# MCU_IO.net
KiCad netlist of a schematic drawn in Altium Designer
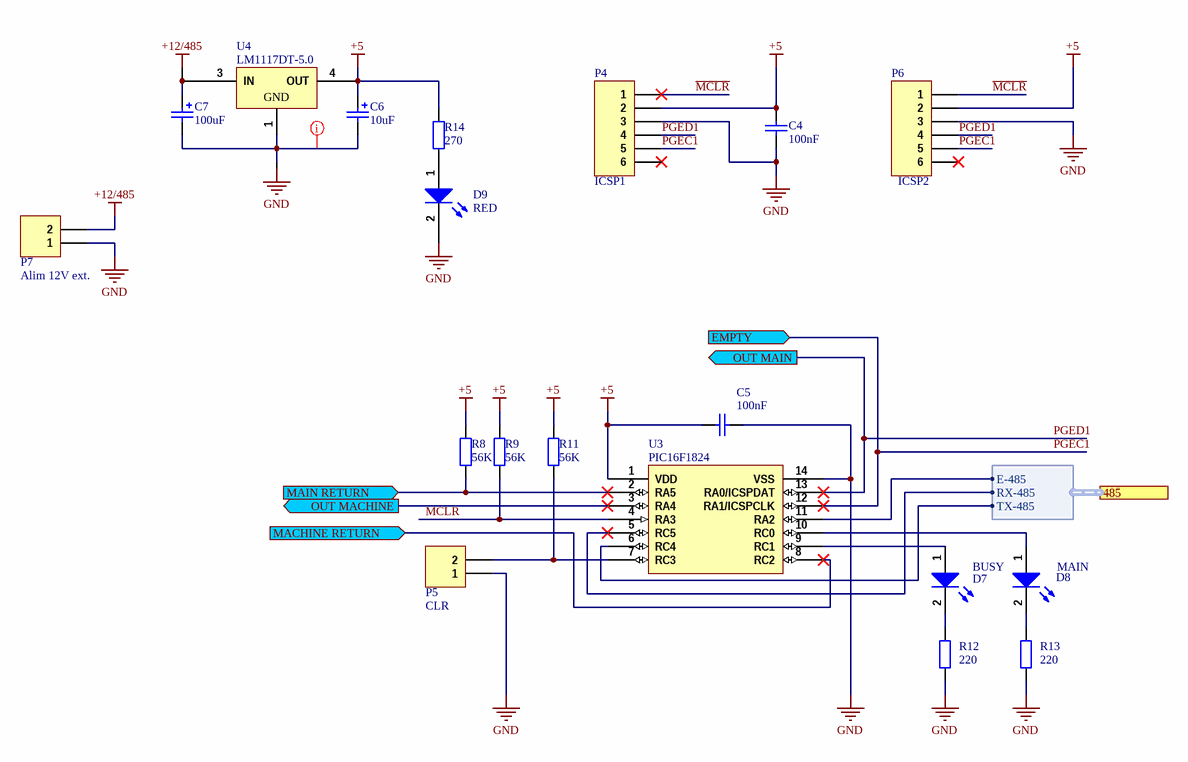
[diagram p0: MCU IO.SchDoc]

(export (version "E")
  (design (tool "Eeschema 10.0.6"))
  (components
    (comp (ref "C4")
      (value "100nF")
      (footprint "SYLANN:C0805")
      (description "Capacitor")
      (fields
        (field (name "MANUFACTURER") "MULTICOMP")
        (field (name "MANUFACTURER PART NUMBER") "MCCA000296")
      )
      (libsource (lib "Capacitors") (part "Cap 0805 100nF"))
    )
    (comp (ref "C5")
      (value "100nF")
      (footprint "SYLANN:C0805")
      (description "Capacitor")
      (fields
        (field (name "MANUFACTURER") "MULTICOMP")
        (field (name "MANUFACTURER PART NUMBER") "MCCA000296")
      )
      (libsource (lib "BRA") (part "Cap 0805 100nF"))
    )
    (comp (ref "C6")
      (value "10uF")
      (footprint "SYLANN:KEMET_4")
      (description "Polarized Capacitor")
      (fields
        (field (name "MANUFACTURER") "KEMET")
        (field (name "MANUFACTURER PART NUMBER") "EXV106M025A9BAA")
      )
      (libsource (lib "BRA") (part "Cap Pol 10uF"))
    )
    (comp (ref "C7")
      (value "100uF")
      (footprint "SYLANN:Kemet_63")
      (description "Polarized Capacitor")
      (fields
        (field (name "MANUFACTURER") "EPCOS")
        (field (name "MANUFACTURER PART NUMBER") "B41142A4107M")
        (field (name "HAUTEUR") "7.7")
        (field (name "LONGUEUR/HAUTEUR") "7.7")
      )
      (libsource (lib "BRA") (part "Cap Pol 100uF"))
    )
    (comp (ref "D7")
      (value "HSMH-C190")
      (footprint "0603-LEDR")
      (description "Surface Mount Chip LED, Red")
      (fields
        (field (name "MANUFACTURER") "AVAGO TECHNOLOGIES")
        (field (name "MANUFACTURER PART NUMBER") "HSMH-C190.")
        (field (name "INDICATOR") "BUSY")
        (field (name "LONGUEUR/HAUTEUR") "1.6")
      )
      (libsource (lib "BRA") (part "HSMH-C190"))
    )
    (comp (ref "D8")
      (value "MAIN")
      (footprint "0603-LEDV")
      (description "Surface Mount Chip GREEN")
      (fields
        (field (name "MANUFACTURER") "Broadcom Avago")
        (field (name "MANUFACTURER PART NUMBER") "HSMG-C190")
      )
      (libsource (lib "BRA") (part "HSMG-C190"))
    )
    (comp (ref "D9")
      (value "HSMH-C190")
      (footprint "0603-LEDR")
      (description "Surface Mount Chip LED, Red")
      (fields
        (field (name "MANUFACTURER") "AVAGO TECHNOLOGIES")
        (field (name "MANUFACTURER PART NUMBER") "HSMH-C190.")
        (field (name "COULEUR") "RED")
        (field (name "LONGUEUR/HAUTEUR") "1.6")
      )
      (libsource (lib "Avago Optoelectronic LED") (part "HSMH-C190"))
    )
    (comp (ref "P4")
      (value "ICSP1")
      (footprint "TC2030")
      (description "Header, 6-Pin")
      (fields (field (name "MANUFACTURER") "HARWIN") (field (name "MANUFACTURER PART NUMBER") "M20-8770642"))
      (libsource (lib "Miscellaneous Connectors") (part "Header 6"))
    )
    (comp (ref "P5")
      (value "CLR")
      (footprint "SYLANN:M20_1X2")
      (description "Header, 2-Pin")
      (fields
        (field (name "MANUFACTURER") "HARWIN")
        (field (name "MANUFACTURER PART NUMBER") "M20-8770242")
        (field (name "PUBLISHER") "Altium Limited")
      )
      (libsource (lib "Miscellaneous Connectors") (part "Header 2"))
    )
    (comp (ref "P6")
      (value "ICSP2")
      (footprint "6SIP100")
      (description "Header, 6-Pin")
      (fields
        (field (name "MANUFACTURER") "TE CONNECTIVITY / AMP")
        (field (name "MANUFACTURER PART NUMBER") "4-103321-8.")
      )
      (libsource (lib "Miscellaneous Connectors") (part "Header 6"))
    )
    (comp (ref "P7")
      (value "Alim 12V ext.")
      (footprint "CO2P508")
      (description "Header, 2-Pin")
      (libsource (lib "Miscellaneous Connectors") (part "Header 2"))
    )
    (comp (ref "R8")
      (value "56K")
      (footprint "R0805")
      (description "Resistor")
      (fields
        (field (name "MANUFACTURER") "MULTICOMP")
        (field (name "MANUFACTURER PART NUMBER") "MC0.1W08051%56KFR")
      )
      (libsource (lib "BRA") (part "Resistor 0805 56K"))
    )
    (comp (ref "R9")
      (value "56K")
      (footprint "R0805")
      (description "Resistor")
      (fields
        (field (name "MANUFACTURER") "MULTICOMP")
        (field (name "MANUFACTURER PART NUMBER") "MC0.1W08051%56KFR")
      )
      (libsource (lib "BRA") (part "Resistor 0805 56K"))
    )
    (comp (ref "R11")
      (value "56K")
      (footprint "R0805")
      (description "Resistor")
      (fields
        (field (name "MANUFACTURER") "MULTICOMP")
        (field (name "MANUFACTURER PART NUMBER") "MC0.1W08051%56KFR")
      )
      (libsource (lib "BRA") (part "Resistor 0805 56K"))
    )
    (comp (ref "R12")
      (value "220")
      (footprint "R0805")
      (description "Resistor")
      (fields
        (field (name "MANUFACTURER") "MULTICOMP")
        (field (name "MANUFACTURER PART NUMBER") "MC01W08051220R")
      )
      (libsource (lib "BRA") (part "Resistor 0805 220"))
    )
    (comp (ref "R13")
      (value "220")
      (footprint "R0805")
      (description "Resistor")
      (fields
        (field (name "MANUFACTURER") "MULTICOMP")
        (field (name "MANUFACTURER PART NUMBER") "MC01W08051220R")
      )
      (libsource (lib "BRA") (part "Resistor 0805 220"))
    )
    (comp (ref "R14")
      (value "270")
      (footprint "R0805")
      (description "Resistor")
      (fields
        (field (name "MANUFACTURER") "MULTICOMP")
        (field (name "MANUFACTURER PART NUMBER") "MC0.1W08051%1KFR")
      )
      (libsource (lib "BRA") (part "Resistor 0805 1K"))
    )
    (comp (ref "U3")
      (value "PIC16F1824")
      (footprint "so-14")
      (description "14 Pin Flash Microcontrollers with XLP Technology")
      (fields
        (field (name "MANUFACTURER") "MICROCHIP")
        (field (name "MANUFACTURER PART NUMBER") "PIC16F1824-I/SL")
      )
      (libsource (lib "BRA") (part "PIC16(L)F1824"))
    )
    (comp (ref "U4")
      (value "LM1117DT-5.0")
      (footprint "SOT223")
      (description "800mA Low-Dropout Linear Regulator, 3-pin TO-252")
      (fields
        (field (name "MANUFACTURER") "TEXAS INSTRUMENTS")
        (field (name "MANUFACTURER PART NUMBER") "LM1117MP-5.0")
      )
      (libsource (lib "NSC LDO") (part "LM1117DT-5.0"))
    )
  )
  (nets
    (net (code "2") (name "+5") (class "Default")
      (node (ref "C4") (pin "2") (pinfunction "2_2") (pintype "passive"))
      (node (ref "C5") (pin "2") (pinfunction "2_2") (pintype "passive"))
      (node (ref "C6") (pin "1") (pinfunction "1_1") (pintype "passive"))
      (node (ref "P4") (pin "2") (pinfunction "2_2") (pintype "passive"))
      (node (ref "P6") (pin "2") (pinfunction "2_2") (pintype "passive"))
      (node (ref "R11") (pin "2") (pinfunction "2_2") (pintype "passive"))
      (node (ref "R14") (pin "2") (pinfunction "2_2") (pintype "passive"))
      (node (ref "R8") (pin "2") (pinfunction "2_2") (pintype "passive"))
      (node (ref "R9") (pin "2") (pinfunction "2_2") (pintype "passive"))
      (node (ref "U3") (pin "1") (pinfunction "VDD_1") (pintype "power_in"))
      (node (ref "U4") (pin "4") (pinfunction "OUT_4") (pintype "power_in"))
    )
    (net (code "3") (name "+12{slash}485") (class "Default")
      (node (ref "C7") (pin "1") (pinfunction "1_1") (pintype "passive"))
      (node (ref "P7") (pin "2") (pinfunction "2_2") (pintype "passive"))
      (node (ref "U4") (pin "3") (pinfunction "IN_3") (pintype "power_in"))
    )
    (net (code "4") (name "/E-485") (class "Default")
      (node (ref "U3") (pin "11") (pinfunction "RA2_11") (pintype "bidirectional"))
    )
    (net (code "5") (name "/MACHINE RETURN") (class "Default")
      (node (ref "U3") (pin "8") (pinfunction "RC2_8") (pintype "bidirectional+no_connect"))
    )
    (net (code "6") (name "/MAIN RETURN") (class "Default")
      (node (ref "R8") (pin "1") (pinfunction "1_1") (pintype "passive"))
      (node (ref "U3") (pin "2") (pinfunction "RA5_2") (pintype "bidirectional"))
    )
    (net (code "7") (name "/OUT MACHINE") (class "Default")
      (node (ref "U3") (pin "3") (pinfunction "RA4_3") (pintype "bidirectional+no_connect"))
    )
    (net (code "8") (name "/PGEC1") (class "Default")
      (node (ref "P4") (pin "5") (pinfunction "5_5") (pintype "passive"))
      (node (ref "P6") (pin "5") (pinfunction "5_5") (pintype "passive"))
      (node (ref "U3") (pin "12") (pinfunction "RA1/ICSPCLK_12") (pintype "bidirectional"))
    )
    (net (code "9") (name "/PGED1") (class "Default")
      (node (ref "P4") (pin "4") (pinfunction "4_4") (pintype "passive"))
      (node (ref "P6") (pin "4") (pinfunction "4_4") (pintype "passive"))
      (node (ref "U3") (pin "13") (pinfunction "RA0/ICSPDAT_13") (pintype "bidirectional"))
    )
    (net (code "10") (name "/RX-485") (class "Default")
      (node (ref "U3") (pin "5") (pinfunction "RC5_5") (pintype "bidirectional+no_connect"))
    )
    (net (code "11") (name "/TX-485") (class "Default")
      (node (ref "U3") (pin "6") (pinfunction "RC4_6") (pintype "bidirectional"))
    )
    (net (code "13") (name "/~{MCLR}") (class "Default")
      (node (ref "P4") (pin "1") (pinfunction "1_1") (pintype "passive"))
      (node (ref "P6") (pin "1") (pinfunction "1_1") (pintype "passive"))
      (node (ref "R9") (pin "1") (pinfunction "1_1") (pintype "passive"))
      (node (ref "U3") (pin "4") (pinfunction "RA3_4") (pintype "input"))
    )
    (net (code "14") (name "GND") (class "Default")
      (node (ref "C4") (pin "1") (pinfunction "1_1") (pintype "passive"))
      (node (ref "C5") (pin "1") (pinfunction "1_1") (pintype "passive"))
      (node (ref "C6") (pin "2") (pinfunction "2_2") (pintype "passive"))
      (node (ref "C7") (pin "2") (pinfunction "2_2") (pintype "passive"))
      (node (ref "D9") (pin "2") (pinfunction "K_2") (pintype "passive"))
      (node (ref "P4") (pin "3") (pinfunction "3_3") (pintype "passive"))
      (node (ref "P5") (pin "1") (pinfunction "1_1") (pintype "passive"))
      (node (ref "P6") (pin "3") (pinfunction "3_3") (pintype "passive"))
      (node (ref "P7") (pin "1") (pinfunction "1_1") (pintype "passive"))
      (node (ref "R12") (pin "1") (pinfunction "1_1") (pintype "passive"))
      (node (ref "R13") (pin "1") (pinfunction "1_1") (pintype "passive"))
      (node (ref "U3") (pin "14") (pinfunction "VSS_14") (pintype "power_in"))
      (node (ref "U4") (pin "1") (pinfunction "GND_1") (pintype "power_in"))
    )
    (net (code "15") (name "Net-(D7-A)") (class "Default")
      (node (ref "D7") (pin "1") (pinfunction "A_1") (pintype "passive"))
      (node (ref "U3") (pin "9") (pinfunction "RC1_9") (pintype "bidirectional"))
    )
    (net (code "16") (name "Net-(D7-K)") (class "Default")
      (node (ref "D7") (pin "2") (pinfunction "K_2") (pintype "passive"))
      (node (ref "R12") (pin "2") (pinfunction "2_2") (pintype "passive"))
    )
    (net (code "17") (name "Net-(D8-A)") (class "Default")
      (node (ref "D8") (pin "1") (pinfunction "A_1") (pintype "passive"))
      (node (ref "U3") (pin "10") (pinfunction "RC0_10") (pintype "bidirectional"))
    )
    (net (code "18") (name "Net-(D8-K)") (class "Default")
      (node (ref "D8") (pin "2") (pinfunction "K_2") (pintype "passive"))
      (node (ref "R13") (pin "2") (pinfunction "2_2") (pintype "passive"))
    )
    (net (code "19") (name "Net-(D9-A)") (class "Default")
      (node (ref "D9") (pin "1") (pinfunction "A_1") (pintype "passive"))
      (node (ref "R14") (pin "1") (pinfunction "1_1") (pintype "passive"))
    )
    (net (code "20") (name "Net-(U3-RC3)") (class "Default")
      (node (ref "P5") (pin "2") (pinfunction "2_2") (pintype "passive"))
      (node (ref "R11") (pin "1") (pinfunction "1_1") (pintype "passive"))
      (node (ref "U3") (pin "7") (pinfunction "RC3_7") (pintype "bidirectional"))
    )
    (net (code "21") (name "unconnected-(P4-Pad6)") (class "Default")
      (node (ref "P4") (pin "6") (pinfunction "6_6") (pintype "passive+no_connect"))
    )
    (net (code "22") (name "unconnected-(P6-Pad6)") (class "Default")
      (node (ref "P6") (pin "6") (pinfunction "6_6") (pintype "passive+no_connect"))
    )
  )
)
